# Page_1.net
KiCad netlist of a schematic drawn in Altium Designer
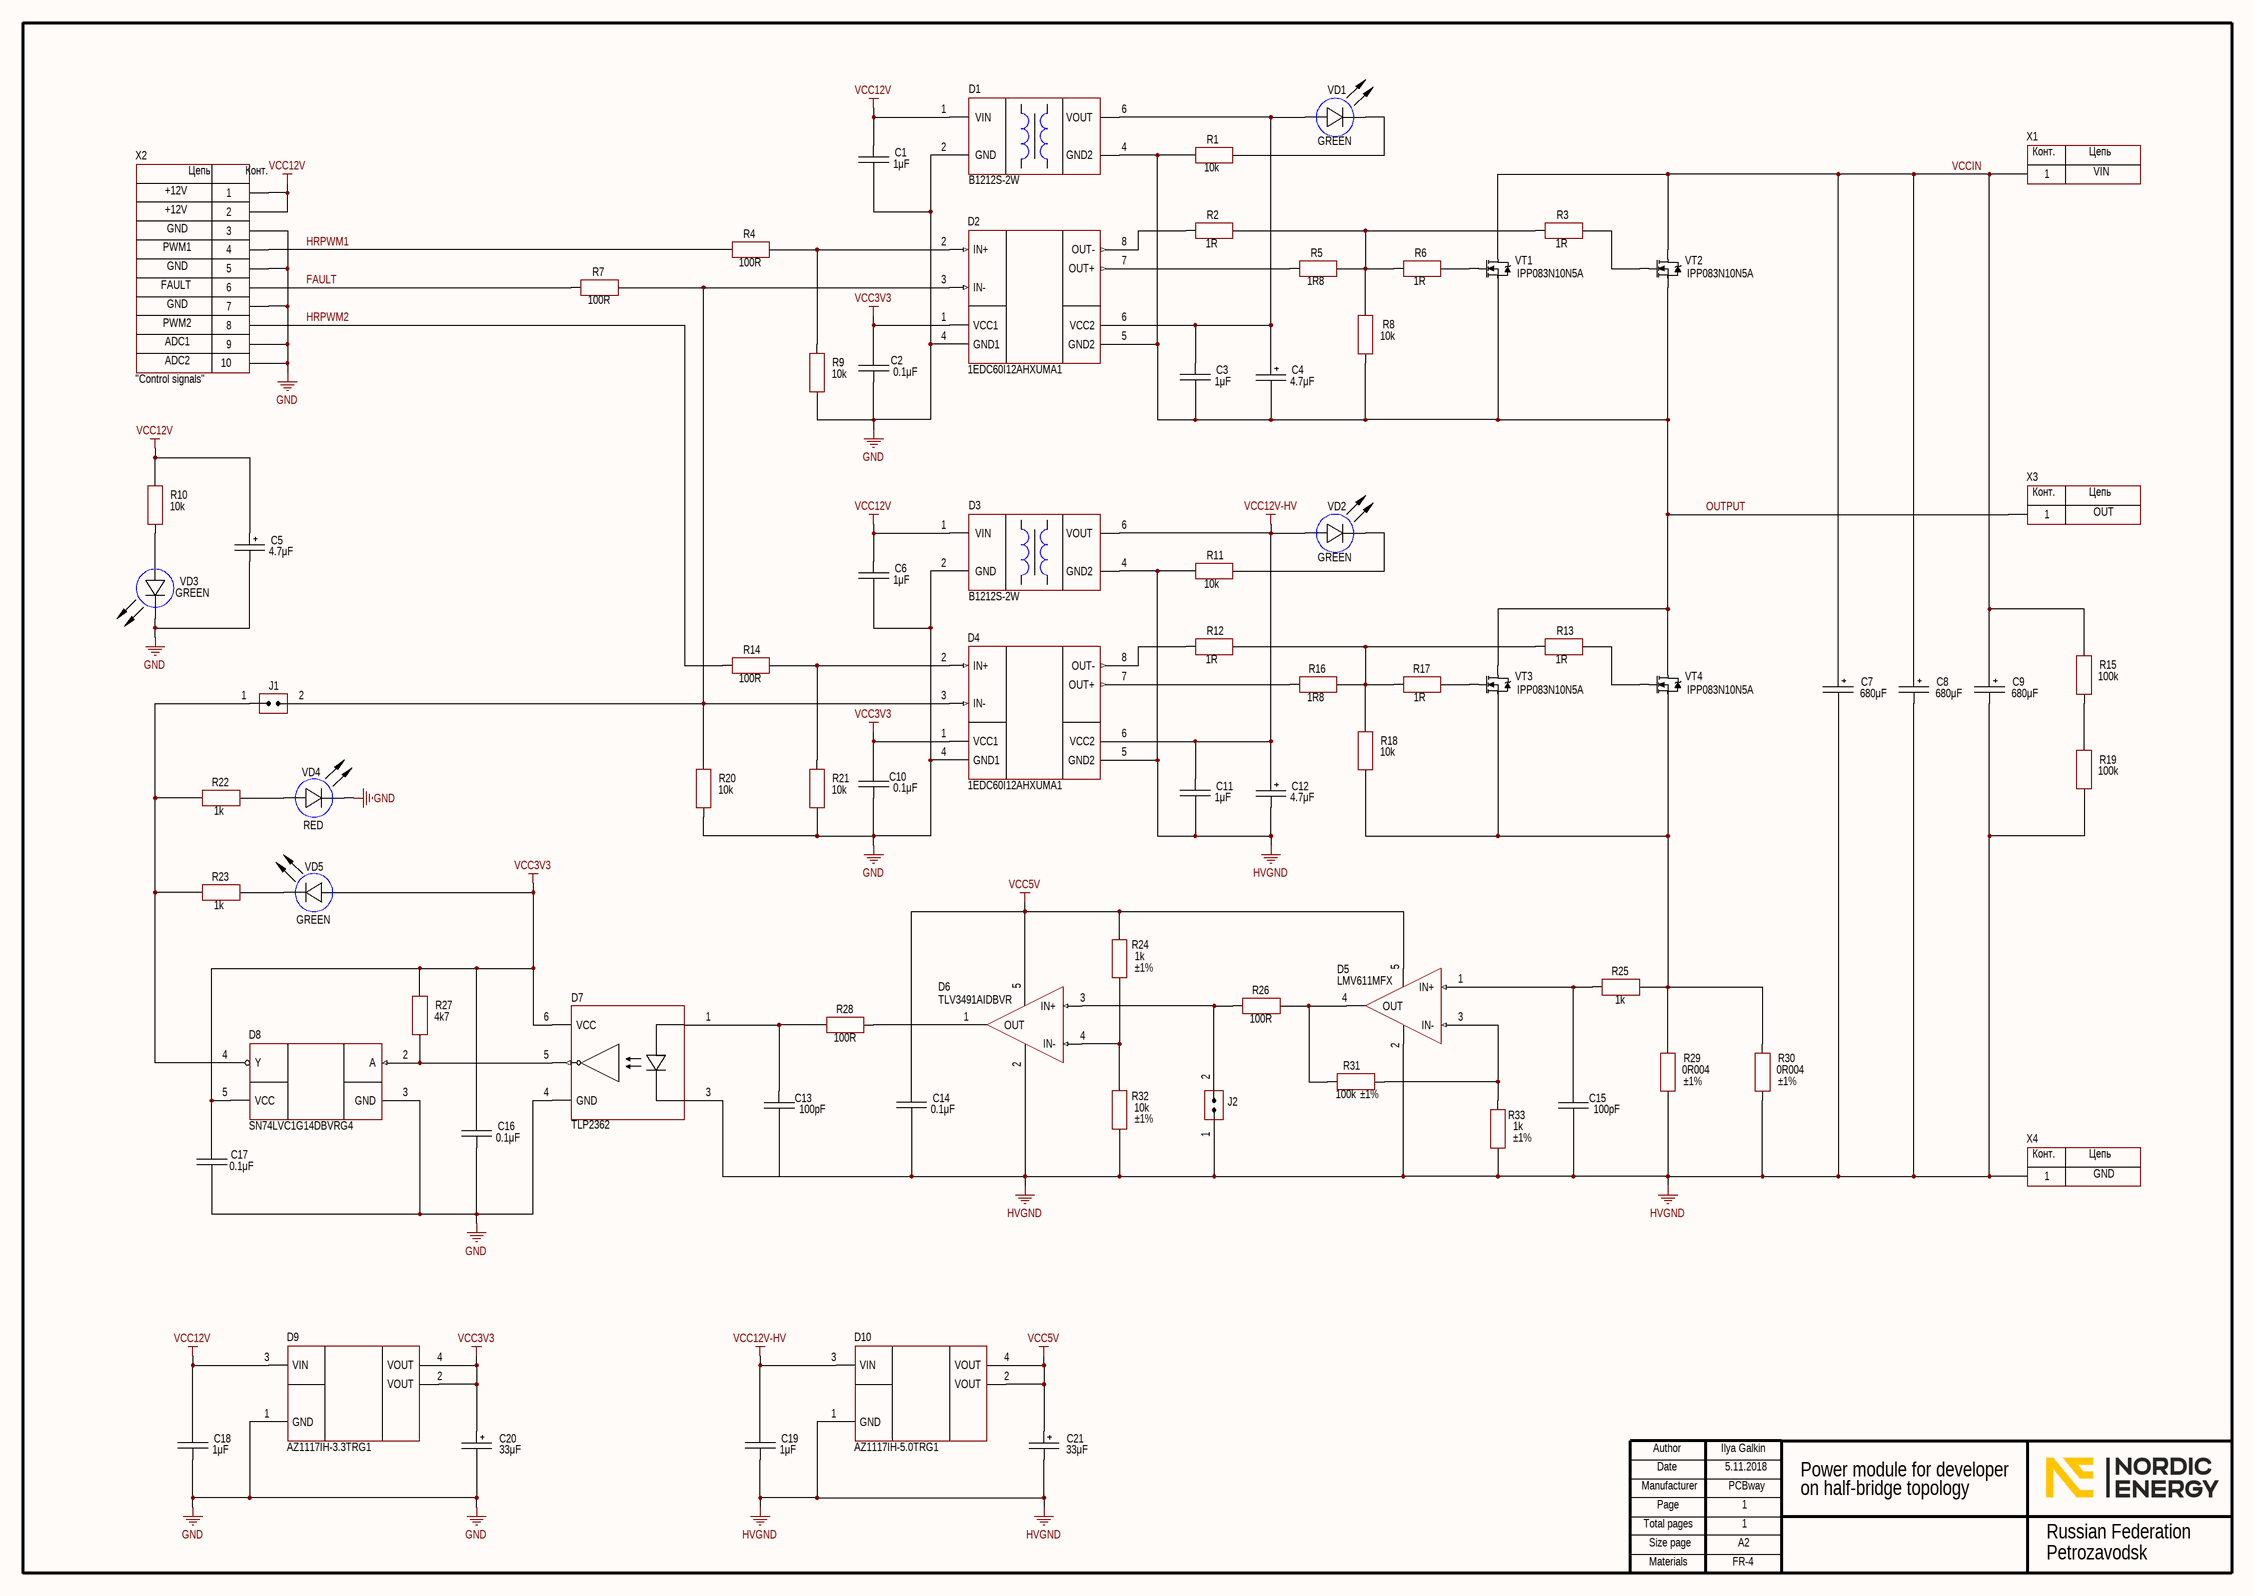
[diagram p0: Page 1.SchDoc]

(export (version "E")
  (design (tool "Eeschema 10.0.6"))
  (components
    (comp (ref "C1")
      (value "1μF")
      (footprint "CH0805C")
      (fields (field (name "MANUFACTURER") "Yageo"))
      (libsource (lib "Discrete") (part "Capacitor"))
    )
    (comp (ref "C2")
      (value "0.1μF")
      (footprint "CH0805C")
      (fields (field (name "MANUFACTURER") "Yageo"))
      (libsource (lib "Discrete") (part "Capacitor"))
    )
    (comp (ref "C3")
      (value "1μF")
      (footprint "CH0805C")
      (fields (field (name "MANUFACTURER") "Yageo"))
      (libsource (lib "Discrete") (part "Capacitor"))
    )
    (comp (ref "C4")
      (value "4.7μF")
      (footprint "TANTAL_A")
      (fields (field (name "MANUFACTURER") "KEMET"))
      (libsource (lib "Discrete") (part "TantalCap"))
    )
    (comp (ref "C5")
      (value "4.7μF")
      (footprint "TANTAL_A")
      (fields (field (name "MANUFACTURER") "KEMET"))
      (libsource (lib "Discrete") (part "TantalCap"))
    )
    (comp (ref "C6")
      (value "1μF")
      (footprint "CH0805C")
      (fields (field (name "MANUFACTURER") "Yageo"))
      (libsource (lib "Discrete") (part "Capacitor"))
    )
    (comp (ref "C7")
      (value "680μF")
      (footprint "D22C10.5H25")
      (fields (field (name "MANUFACTURER") "Yageo"))
      (libsource (lib "Discrete") (part "AlumCap"))
    )
    (comp (ref "C8")
      (value "680μF")
      (footprint "D22C10.5H25")
      (fields (field (name "MANUFACTURER") "Yageo"))
      (libsource (lib "Discrete") (part "AlumCap"))
    )
    (comp (ref "C9")
      (value "680μF")
      (footprint "D22C10.5H25")
      (fields (field (name "MANUFACTURER") "Yageo"))
      (libsource (lib "Discrete") (part "AlumCap"))
    )
    (comp (ref "C10")
      (value "0.1μF")
      (footprint "CH0805C")
      (fields (field (name "MANUFACTURER") "Yageo"))
      (libsource (lib "Discrete") (part "Capacitor"))
    )
    (comp (ref "C11")
      (value "1μF")
      (footprint "CH0805C")
      (fields (field (name "MANUFACTURER") "Yageo"))
      (libsource (lib "Discrete") (part "Capacitor"))
    )
    (comp (ref "C12")
      (value "4.7μF")
      (footprint "TANTAL_A")
      (fields (field (name "MANUFACTURER") "KEMET"))
      (libsource (lib "Discrete") (part "TantalCap"))
    )
    (comp (ref "C13")
      (value "100pF")
      (footprint "CH0805C")
      (fields (field (name "MANUFACTURER") "Yageo"))
      (libsource (lib "Discrete") (part "Capacitor"))
    )
    (comp (ref "C14")
      (value "0.1μF")
      (footprint "CH0805C")
      (fields (field (name "MANUFACTURER") "Yageo"))
      (libsource (lib "Discrete") (part "Capacitor"))
    )
    (comp (ref "C15")
      (value "100pF")
      (footprint "CH0805C")
      (fields (field (name "MANUFACTURER") "Yageo"))
      (libsource (lib "Discrete") (part "Capacitor"))
    )
    (comp (ref "C16")
      (value "0.1μF")
      (footprint "CH0805C")
      (fields (field (name "MANUFACTURER") "Yageo"))
      (libsource (lib "Discrete") (part "Capacitor"))
    )
    (comp (ref "C17")
      (value "0.1μF")
      (footprint "CH0805C")
      (fields (field (name "MANUFACTURER") "Yageo"))
      (libsource (lib "Discrete") (part "Capacitor"))
    )
    (comp (ref "C18")
      (value "1μF")
      (footprint "CH0805C")
      (fields (field (name "MANUFACTURER") "Yageo"))
      (libsource (lib "Discrete") (part "Capacitor"))
    )
    (comp (ref "C19")
      (value "1μF")
      (footprint "CH0805C")
      (fields (field (name "MANUFACTURER") "Yageo"))
      (libsource (lib "Discrete") (part "Capacitor"))
    )
    (comp (ref "C20")
      (value "33μF")
      (footprint "TANTAL_A")
      (fields (field (name "MANUFACTURER") "AVX"))
      (libsource (lib "Discrete") (part "TantalCap"))
    )
    (comp (ref "C21")
      (value "33μF")
      (footprint "TANTAL_A")
      (fields (field (name "MANUFACTURER") "AVX"))
      (libsource (lib "Discrete") (part "TantalCap"))
    )
    (comp (ref "D1")
      (value "B1212S-2W")
      (footprint "MOD: TMA-0505S")
      (description "Isolator DC")
      (fields (field (name "MANUFACTURER") "Mornsun"))
      (libsource (lib "Module") (part "TMA-0505S"))
    )
    (comp (ref "D2")
      (value "1EDC60I12AHXUMA1")
      (footprint "8-SO (300 mill)")
      (description "Driver")
      (fields (field (name "MANUFACTURER") "Infineon Technologies"))
      (libsource (lib "Power Supplies") (part "1EDC60I12AHXUMA1"))
    )
    (comp (ref "D3")
      (value "B1212S-2W")
      (footprint "MOD: TMA-0505S")
      (description "Isolator DC")
      (fields (field (name "MANUFACTURER") "Mornsun"))
      (libsource (lib "Module") (part "TMA-0505S"))
    )
    (comp (ref "D4")
      (value "1EDC60I12AHXUMA1")
      (footprint "8-SO (300 mill)")
      (description "Driver")
      (fields (field (name "MANUFACTURER") "Infineon Technologies"))
      (libsource (lib "Power Supplies") (part "1EDC60I12AHXUMA1"))
    )
    (comp (ref "D5")
      (value "LMV611MFX")
      (footprint "SOT23-5")
      (description "Amplifer")
      (fields (field (name "MANUFACTURER") "Texas Instruments"))
      (libsource (lib "Analog") (part "LMV611MFX"))
    )
    (comp (ref "D6")
      (value "TLV3491AIDBVR")
      (footprint "SOT23-5")
      (description "Comparator")
      (fields (field (name "MANUFACTURER") "Texas Instruments"))
      (libsource (lib "Analog") (part "TLV3491AIDBVR"))
    )
    (comp (ref "D7")
      (value "TLP2362")
      (footprint "OPTO: TLP2362")
      (description "Optoisolator")
      (fields (field (name "MANUFACTURER") "Toshiba"))
      (libsource (lib "Power Supplies") (part "TLP2362"))
    )
    (comp (ref "D8")
      (value "SN74LVC1G14DBVRG4")
      (footprint "SOT23-5")
      (description "Inverter logic")
      (fields (field (name "MANUFACTURER") "Texas Instruments"))
      (libsource (lib "Analog") (part "SN74LVC1G14DBVRG4"))
    )
    (comp (ref "D9")
      (value "AZ1117IH-3.3TRG1")
      (footprint "SOT223")
      (description "LDO")
      (fields (field (name "MANUFACTURER") "Diodes Incorporated"))
      (libsource (lib "Power Supplies") (part "LDL1117S33R"))
    )
    (comp (ref "D10")
      (value "AZ1117IH-5.0TRG1")
      (footprint "SOT223")
      (description "LDO")
      (fields (field (name "MANUFACTURER") "Diodes Incorporated"))
      (libsource (lib "Power Supplies") (part "LDL1117S33R"))
    )
    (comp (ref "J1")
      (value "Jumper-2")
      (footprint "CON: PLS-2")
      (description "Jumper")
      (fields (field (name "MANUFACTURER") "China"))
      (libsource (lib "Connectors") (part "Jumper-2"))
    )
    (comp (ref "J2")
      (value "Jumper-2")
      (footprint "CON: PLS-2")
      (description "Jumper")
      (fields (field (name "MANUFACTURER") "China"))
      (libsource (lib "") (part "Jumper-2_1"))
    )
    (comp (ref "R1")
      (value "10k")
      (footprint "CH0805R")
      (fields (field (name "MANUFACTURER") "Yageo"))
      (libsource (lib "") (part "Resistor_2"))
    )
    (comp (ref "R2")
      (value "1R")
      (footprint "CH0805R")
      (fields (field (name "MANUFACTURER") "Yageo"))
      (libsource (lib "Discrete") (part "Resistor"))
    )
    (comp (ref "R3")
      (value "1R")
      (footprint "CH0805R")
      (fields (field (name "MANUFACTURER") "Yageo"))
      (libsource (lib "Discrete") (part "Resistor"))
    )
    (comp (ref "R4")
      (value "100R")
      (footprint "CH0805R")
      (fields (field (name "MANUFACTURER") "Yageo"))
      (libsource (lib "Discrete") (part "Resistor"))
    )
    (comp (ref "R5")
      (value "1R8")
      (footprint "CH0805R")
      (fields (field (name "MANUFACTURER") "Yageo"))
      (libsource (lib "Discrete") (part "Resistor"))
    )
    (comp (ref "R6")
      (value "1R")
      (footprint "CH0805R")
      (fields (field (name "MANUFACTURER") "Yageo"))
      (libsource (lib "Discrete") (part "Resistor"))
    )
    (comp (ref "R7")
      (value "100R")
      (footprint "CH0805R")
      (fields (field (name "MANUFACTURER") "Yageo"))
      (libsource (lib "Discrete") (part "Resistor"))
    )
    (comp (ref "R8")
      (value "10k")
      (footprint "CH0805R")
      (fields (field (name "MANUFACTURER") "Yageo"))
      (libsource (lib "") (part "Resistor_1"))
    )
    (comp (ref "R9")
      (value "10k")
      (footprint "CH0805R")
      (fields (field (name "MANUFACTURER") "Yageo"))
      (libsource (lib "") (part "Resistor_1"))
    )
    (comp (ref "R10")
      (value "10k")
      (footprint "CH0805R")
      (fields (field (name "MANUFACTURER") "Yageo"))
      (libsource (lib "") (part "Resistor_1"))
    )
    (comp (ref "R11")
      (value "10k")
      (footprint "CH0805R")
      (fields (field (name "MANUFACTURER") "Yageo"))
      (libsource (lib "") (part "Resistor_2"))
    )
    (comp (ref "R12")
      (value "1R")
      (footprint "CH0805R")
      (fields (field (name "MANUFACTURER") "Yageo"))
      (libsource (lib "Discrete") (part "Resistor"))
    )
    (comp (ref "R13")
      (value "1R")
      (footprint "CH0805R")
      (fields (field (name "MANUFACTURER") "Yageo"))
      (libsource (lib "Discrete") (part "Resistor"))
    )
    (comp (ref "R14")
      (value "100R")
      (footprint "CH0805R")
      (fields (field (name "MANUFACTURER") "Yageo"))
      (libsource (lib "Discrete") (part "Resistor"))
    )
    (comp (ref "R15")
      (value "100k")
      (footprint "CH1206R")
      (fields (field (name "MANUFACTURER") "Yageo"))
      (libsource (lib "") (part "Resistor_1"))
    )
    (comp (ref "R16")
      (value "1R8")
      (footprint "CH0805R")
      (fields (field (name "MANUFACTURER") "Yageo"))
      (libsource (lib "Discrete") (part "Resistor"))
    )
    (comp (ref "R17")
      (value "1R")
      (footprint "CH0805R")
      (fields (field (name "MANUFACTURER") "Yageo"))
      (libsource (lib "Discrete") (part "Resistor"))
    )
    (comp (ref "R18")
      (value "10k")
      (footprint "CH0805R")
      (fields (field (name "MANUFACTURER") "Yageo"))
      (libsource (lib "") (part "Resistor_1"))
    )
    (comp (ref "R19")
      (value "100k")
      (footprint "CH1206R")
      (fields (field (name "MANUFACTURER") "Yageo"))
      (libsource (lib "") (part "Resistor_1"))
    )
    (comp (ref "R20")
      (value "10k")
      (footprint "CH0805R")
      (fields (field (name "MANUFACTURER") "Yageo"))
      (libsource (lib "") (part "Resistor_1"))
    )
    (comp (ref "R21")
      (value "10k")
      (footprint "CH0805R")
      (fields (field (name "MANUFACTURER") "Yageo"))
      (libsource (lib "") (part "Resistor_1"))
    )
    (comp (ref "R22")
      (value "1k")
      (footprint "CH0805R")
      (fields (field (name "MANUFACTURER") "Yageo"))
      (libsource (lib "") (part "Resistor_2"))
    )
    (comp (ref "R23")
      (value "1k")
      (footprint "CH0805R")
      (fields (field (name "MANUFACTURER") "Yageo"))
      (libsource (lib "") (part "Resistor_2"))
    )
    (comp (ref "R24")
      (value "1k")
      (footprint "CH0805R")
      (fields (field (name "MANUFACTURER") "Yageo") (field (name "COMPONENTKIND") "±1%"))
      (libsource (lib "Discrete") (part "Resistor"))
    )
    (comp (ref "R25")
      (value "1k")
      (footprint "CH0805R")
      (fields (field (name "MANUFACTURER") "Yageo"))
      (libsource (lib "Discrete") (part "Resistor"))
    )
    (comp (ref "R26")
      (value "100R")
      (footprint "CH0805R")
      (fields (field (name "MANUFACTURER") "Yageo"))
      (libsource (lib "Discrete") (part "Resistor"))
    )
    (comp (ref "R27")
      (value "4k7")
      (footprint "CH0805R")
      (fields (field (name "MANUFACTURER") "Yageo"))
      (libsource (lib "") (part "Resistor_1"))
    )
    (comp (ref "R28")
      (value "100R")
      (footprint "CH0805R")
      (fields (field (name "MANUFACTURER") "Yageo"))
      (libsource (lib "Discrete") (part "Resistor"))
    )
    (comp (ref "R29")
      (value "0R004")
      (footprint "CH2512R")
      (fields (field (name "MANUFACTURER") "Yageo") (field (name "COMPONENTKIND") "±1%"))
      (libsource (lib "") (part "Resistor_3"))
    )
    (comp (ref "R30")
      (value "0R004")
      (footprint "CH2512R")
      (fields (field (name "MANUFACTURER") "Yageo") (field (name "COMPONENTKIND") "±1%"))
      (libsource (lib "") (part "Resistor_3"))
    )
    (comp (ref "R31")
      (value "100k")
      (footprint "CH0805R")
      (fields (field (name "MANUFACTURER") "Yageo") (field (name "COMPONENTKIND") "±1%"))
      (libsource (lib "") (part "Resistor_3"))
    )
    (comp (ref "R32")
      (value "10k")
      (footprint "CH0805R")
      (fields (field (name "MANUFACTURER") "Yageo") (field (name "COMPONENTKIND") "±1%"))
      (libsource (lib "Discrete") (part "Resistor"))
    )
    (comp (ref "R33")
      (value "1k")
      (footprint "CH0805R")
      (fields (field (name "MANUFACTURER") "Yageo") (field (name "COMPONENTKIND") "±1%"))
      (libsource (lib "Discrete") (part "Resistor"))
    )
    (comp (ref "VD1")
      (value "GREEN")
      (footprint "CH0805LG")
      (fields (field (name "MANUFACTURER") "Wurth Electronics Inc."))
      (libsource (lib "Discrete") (part "LED"))
    )
    (comp (ref "VD2")
      (value "GREEN")
      (footprint "CH0805LG")
      (fields (field (name "MANUFACTURER") "Wurth Electronics Inc."))
      (libsource (lib "Discrete") (part "LED"))
    )
    (comp (ref "VD3")
      (value "GREEN")
      (footprint "CH0805LG")
      (fields (field (name "MANUFACTURER") "Wurth Electronics Inc."))
      (libsource (lib "Discrete") (part "LED"))
    )
    (comp (ref "VD4")
      (value "RED")
      (footprint "CH0805LR")
      (fields (field (name "MANUFACTURER") "Wurth Electronics Inc."))
      (libsource (lib "Discrete") (part "LED"))
    )
    (comp (ref "VD5")
      (value "GREEN")
      (footprint "CH0805LG")
      (fields (field (name "MANUFACTURER") "Wurth Electronics Inc."))
      (libsource (lib "Discrete") (part "LED"))
    )
    (comp (ref "VT1")
      (value "IPP083N10N5A")
      (footprint "TO220_123")
      (description "Mosfet")
      (fields (field (name "MANUFACTURER") "Infineon"))
      (libsource (lib "Transistor") (part "N-chanel"))
    )
    (comp (ref "VT2")
      (value "IPP083N10N5A")
      (footprint "TO220_123")
      (description "Mosfet")
      (fields (field (name "MANUFACTURER") "Infineon"))
      (libsource (lib "Transistor") (part "N-chanel"))
    )
    (comp (ref "VT3")
      (value "IPP083N10N5A")
      (footprint "TO220_123")
      (description "Mosfet")
      (fields (field (name "MANUFACTURER") "Infineon"))
      (libsource (lib "Transistor") (part "N-chanel"))
    )
    (comp (ref "VT4")
      (value "IPP083N10N5A")
      (footprint "TO220_123")
      (description "Mosfet")
      (fields (field (name "MANUFACTURER") "Infineon"))
      (libsource (lib "Transistor") (part "N-chanel"))
    )
    (comp (ref "X1")
      (value "~")
      (footprint "CON: 10x6 mm")
      (libsource (lib "Connectors") (part "1-Connector"))
    )
    (comp (ref "X2")
      (value "\"Control signals\"")
      (footprint "CON: BH-10")
      (fields (field (name "MANUFACTURER") "Connfly"))
      (libsource (lib "Connectors") (part "10-Connector"))
    )
    (comp (ref "X3")
      (value "~")
      (footprint "CON: 10x6 mm")
      (libsource (lib "Connectors") (part "1-Connector"))
    )
    (comp (ref "X4")
      (value "~")
      (footprint "CON: 10x6 mm")
      (libsource (lib "Connectors") (part "1-Connector"))
    )
  )
  (nets
    (net (code "1") (name "/FAULT") (class "Default")
      (node (ref "R7") (pin "1") (pinfunction "1_1") (pintype "passive"))
      (node (ref "X2") (pin "6") (pinfunction "6_6") (pintype "power_in"))
    )
    (net (code "2") (name "/HRPWM1") (class "Default")
      (node (ref "R4") (pin "1") (pinfunction "1_1") (pintype "passive"))
      (node (ref "X2") (pin "4") (pinfunction "4_4") (pintype "power_in"))
    )
    (net (code "3") (name "/HRPWM2") (class "Default")
      (node (ref "R14") (pin "1") (pinfunction "1_1") (pintype "passive"))
      (node (ref "X2") (pin "8") (pinfunction "8_8") (pintype "power_in"))
    )
    (net (code "4") (name "/OUTPUT") (class "Default")
      (node (ref "C3") (pin "1") (pinfunction "1_1") (pintype "power_in"))
      (node (ref "C4") (pin "2") (pinfunction "2_2") (pintype "power_in"))
      (node (ref "D1") (pin "4") (pinfunction "GND2_4") (pintype "power_in"))
      (node (ref "D2") (pin "5") (pinfunction "GND2_5") (pintype "passive"))
      (node (ref "R1") (pin "2") (pinfunction "2_2") (pintype "passive"))
      (node (ref "R8") (pin "1") (pinfunction "1_1") (pintype "passive"))
      (node (ref "VT1") (pin "3") (pinfunction "S_3") (pintype "passive"))
      (node (ref "VT2") (pin "3") (pinfunction "S_3") (pintype "passive"))
      (node (ref "VT3") (pin "2") (pinfunction "D_2") (pintype "passive"))
      (node (ref "VT4") (pin "2") (pinfunction "D_2") (pintype "passive"))
      (node (ref "X3") (pin "1") (pinfunction "1_1") (pintype "passive"))
    )
    (net (code "5") (name "/VCCIN") (class "Default")
      (node (ref "C7") (pin "1") (pinfunction "1_1") (pintype "power_in"))
      (node (ref "C8") (pin "1") (pinfunction "1_1") (pintype "power_in"))
      (node (ref "C9") (pin "1") (pinfunction "1_1") (pintype "power_in"))
      (node (ref "R15") (pin "2") (pinfunction "2_2") (pintype "passive"))
      (node (ref "VT1") (pin "2") (pinfunction "D_2") (pintype "passive"))
      (node (ref "VT2") (pin "2") (pinfunction "D_2") (pintype "passive"))
      (node (ref "X1") (pin "1") (pinfunction "1_1") (pintype "passive"))
    )
    (net (code "6") (name "GND") (class "Default")
      (node (ref "C1") (pin "1") (pinfunction "1_1") (pintype "power_in"))
      (node (ref "C10") (pin "1") (pinfunction "1_1") (pintype "power_in"))
      (node (ref "C16") (pin "1") (pinfunction "1_1") (pintype "power_in"))
      (node (ref "C17") (pin "1") (pinfunction "1_1") (pintype "power_in"))
      (node (ref "C18") (pin "1") (pinfunction "1_1") (pintype "power_in"))
      (node (ref "C2") (pin "1") (pinfunction "1_1") (pintype "power_in"))
      (node (ref "C20") (pin "2") (pinfunction "2_2") (pintype "power_in"))
      (node (ref "C5") (pin "2") (pinfunction "2_2") (pintype "power_in"))
      (node (ref "C6") (pin "1") (pinfunction "1_1") (pintype "power_in"))
      (node (ref "D1") (pin "2") (pinfunction "GND_2") (pintype "power_in"))
      (node (ref "D2") (pin "4") (pinfunction "GND1_4") (pintype "passive"))
      (node (ref "D3") (pin "2") (pinfunction "GND_2") (pintype "power_in"))
      (node (ref "D4") (pin "4") (pinfunction "GND1_4") (pintype "passive"))
      (node (ref "D7") (pin "4") (pinfunction "GND_4") (pintype "passive"))
      (node (ref "D8") (pin "3") (pinfunction "GND_3") (pintype "passive"))
      (node (ref "D9") (pin "1") (pinfunction "GND_1") (pintype "power_in"))
      (node (ref "R20") (pin "1") (pinfunction "1_1") (pintype "passive"))
      (node (ref "R21") (pin "1") (pinfunction "1_1") (pintype "passive"))
      (node (ref "R9") (pin "1") (pinfunction "1_1") (pintype "passive"))
      (node (ref "VD3") (pin "2") (pinfunction "C_2") (pintype "passive"))
      (node (ref "VD4") (pin "2") (pinfunction "C_2") (pintype "passive"))
      (node (ref "X2") (pin "10") (pinfunction "10_10") (pintype "power_in"))
      (node (ref "X2") (pin "3") (pinfunction "3_3") (pintype "power_in"))
      (node (ref "X2") (pin "5") (pinfunction "5_5") (pintype "power_in"))
      (node (ref "X2") (pin "7") (pinfunction "7_7") (pintype "power_in"))
      (node (ref "X2") (pin "9") (pinfunction "9_9") (pintype "power_in"))
    )
    (net (code "7") (name "HVGND") (class "Default")
      (node (ref "C11") (pin "1") (pinfunction "1_1") (pintype "power_in"))
      (node (ref "C12") (pin "2") (pinfunction "2_2") (pintype "power_in"))
      (node (ref "C13") (pin "1") (pinfunction "1_1") (pintype "power_in"))
      (node (ref "C14") (pin "1") (pinfunction "1_1") (pintype "power_in"))
      (node (ref "C15") (pin "1") (pinfunction "1_1") (pintype "power_in"))
      (node (ref "C19") (pin "1") (pinfunction "1_1") (pintype "power_in"))
      (node (ref "C21") (pin "2") (pinfunction "2_2") (pintype "power_in"))
      (node (ref "C7") (pin "2") (pinfunction "2_2") (pintype "power_in"))
      (node (ref "C8") (pin "2") (pinfunction "2_2") (pintype "power_in"))
      (node (ref "C9") (pin "2") (pinfunction "2_2") (pintype "power_in"))
      (node (ref "D10") (pin "1") (pinfunction "GND_1") (pintype "power_in"))
      (node (ref "D3") (pin "4") (pinfunction "GND2_4") (pintype "power_in"))
      (node (ref "D4") (pin "5") (pinfunction "GND2_5") (pintype "passive"))
      (node (ref "D5") (pin "2") (pinfunction "V-_2") (pintype "power_in"))
      (node (ref "D6") (pin "2") (pinfunction "V-_2") (pintype "power_in"))
      (node (ref "D7") (pin "3") (pinfunction "C_3") (pintype "passive"))
      (node (ref "J2") (pin "1") (pinfunction "IN_1") (pintype "passive"))
      (node (ref "R11") (pin "2") (pinfunction "2_2") (pintype "passive"))
      (node (ref "R19") (pin "1") (pinfunction "1_1") (pintype "passive"))
      (node (ref "R29") (pin "2") (pinfunction "2_2") (pintype "passive"))
      (node (ref "R30") (pin "2") (pinfunction "2_2") (pintype "passive"))
      (node (ref "R32") (pin "1") (pinfunction "1_1") (pintype "passive"))
      (node (ref "R33") (pin "1") (pinfunction "1_1") (pintype "passive"))
      (node (ref "X4") (pin "1") (pinfunction "1_1") (pintype "passive"))
    )
    (net (code "8") (name "Net-(D1-VOUT)") (class "Default")
      (node (ref "C3") (pin "2") (pinfunction "2_2") (pintype "power_in"))
      (node (ref "C4") (pin "1") (pinfunction "1_1") (pintype "power_in"))
      (node (ref "D1") (pin "6") (pinfunction "VOUT_6") (pintype "power_in"))
      (node (ref "D2") (pin "6") (pinfunction "VCC2_6") (pintype "passive"))
      (node (ref "VD1") (pin "1") (pinfunction "A_1") (pintype "passive"))
    )
    (net (code "9") (name "Net-(D2-IN+)") (class "Default")
      (node (ref "D2") (pin "2") (pinfunction "IN+_2") (pintype "input"))
      (node (ref "R4") (pin "2") (pinfunction "2_2") (pintype "passive"))
      (node (ref "R9") (pin "2") (pinfunction "2_2") (pintype "passive"))
    )
    (net (code "10") (name "Net-(D2-IN-)") (class "Default")
      (node (ref "D2") (pin "3") (pinfunction "IN-_3") (pintype "input"))
      (node (ref "D4") (pin "3") (pinfunction "IN-_3") (pintype "input"))
      (node (ref "J1") (pin "2") (pinfunction "IN_2") (pintype "passive"))
      (node (ref "R20") (pin "2") (pinfunction "2_2") (pintype "passive"))
      (node (ref "R7") (pin "2") (pinfunction "2_2") (pintype "passive"))
    )
    (net (code "11") (name "Net-(D2-OUT+)") (class "Default")
      (node (ref "D2") (pin "7") (pinfunction "OUT+_7") (pintype "output"))
      (node (ref "R5") (pin "1") (pinfunction "1_1") (pintype "passive"))
    )
    (net (code "12") (name "Net-(D2-OUT-)") (class "Default")
      (node (ref "D2") (pin "8") (pinfunction "OUT-_8") (pintype "output"))
      (node (ref "R2") (pin "1") (pinfunction "1_1") (pintype "passive"))
    )
    (net (code "13") (name "Net-(D4-IN+)") (class "Default")
      (node (ref "D4") (pin "2") (pinfunction "IN+_2") (pintype "input"))
      (node (ref "R14") (pin "2") (pinfunction "2_2") (pintype "passive"))
      (node (ref "R21") (pin "2") (pinfunction "2_2") (pintype "passive"))
    )
    (net (code "14") (name "Net-(D4-OUT+)") (class "Default")
      (node (ref "D4") (pin "7") (pinfunction "OUT+_7") (pintype "output"))
      (node (ref "R16") (pin "1") (pinfunction "1_1") (pintype "passive"))
    )
    (net (code "15") (name "Net-(D4-OUT-)") (class "Default")
      (node (ref "D4") (pin "8") (pinfunction "OUT-_8") (pintype "output"))
      (node (ref "R12") (pin "1") (pinfunction "1_1") (pintype "passive"))
    )
    (net (code "16") (name "Net-(D5-IN+)") (class "Default")
      (node (ref "C15") (pin "2") (pinfunction "2_2") (pintype "power_in"))
      (node (ref "D5") (pin "1") (pinfunction "IN+_1") (pintype "input"))
      (node (ref "R25") (pin "1") (pinfunction "1_1") (pintype "passive"))
    )
    (net (code "17") (name "Net-(D5-IN-)") (class "Default")
      (node (ref "D5") (pin "3") (pinfunction "IN-_3") (pintype "input"))
      (node (ref "R31") (pin "1") (pinfunction "1_1") (pintype "passive"))
      (node (ref "R33") (pin "2") (pinfunction "2_2") (pintype "passive"))
    )
    (net (code "18") (name "Net-(D5-OUT)") (class "Default")
      (node (ref "D5") (pin "4") (pinfunction "OUT_4") (pintype "power_in"))
      (node (ref "R26") (pin "2") (pinfunction "2_2") (pintype "passive"))
      (node (ref "R31") (pin "2") (pinfunction "2_2") (pintype "passive"))
    )
    (net (code "19") (name "Net-(D6-IN+)") (class "Default")
      (node (ref "D6") (pin "3") (pinfunction "IN+_3") (pintype "input"))
      (node (ref "J2") (pin "2") (pinfunction "IN_2") (pintype "passive"))
      (node (ref "R26") (pin "1") (pinfunction "1_1") (pintype "passive"))
    )
    (net (code "20") (name "Net-(D6-IN-)") (class "Default")
      (node (ref "D6") (pin "4") (pinfunction "IN-_4") (pintype "input"))
      (node (ref "R24") (pin "1") (pinfunction "1_1") (pintype "passive"))
      (node (ref "R32") (pin "2") (pinfunction "2_2") (pintype "passive"))
    )
    (net (code "21") (name "Net-(D6-OUT)") (class "Default")
      (node (ref "D6") (pin "1") (pinfunction "OUT_1") (pintype "power_in"))
      (node (ref "R28") (pin "2") (pinfunction "2_2") (pintype "passive"))
    )
    (net (code "22") (name "Net-(D7-A)") (class "Default")
      (node (ref "C13") (pin "2") (pinfunction "2_2") (pintype "power_in"))
      (node (ref "D7") (pin "1") (pinfunction "A_1") (pintype "passive"))
      (node (ref "R28") (pin "1") (pinfunction "1_1") (pintype "passive"))
    )
    (net (code "23") (name "Net-(D7-VOUT)") (class "Default")
      (node (ref "D7") (pin "5") (pinfunction "VOUT_5") (pintype "output"))
      (node (ref "D8") (pin "2") (pinfunction "A_2") (pintype "input"))
      (node (ref "R27") (pin "1") (pinfunction "1_1") (pintype "passive"))
    )
    (net (code "24") (name "Net-(D8-Y)") (class "Default")
      (node (ref "D8") (pin "4") (pinfunction "Y_4") (pintype "passive"))
      (node (ref "J1") (pin "1") (pinfunction "IN_1") (pintype "passive"))
      (node (ref "R22") (pin "2") (pinfunction "2_2") (pintype "passive"))
      (node (ref "R23") (pin "2") (pinfunction "2_2") (pintype "passive"))
    )
    (net (code "25") (name "Net-(R2-Pad2)") (class "Default")
      (node (ref "R2") (pin "2") (pinfunction "2_2") (pintype "passive"))
      (node (ref "R3") (pin "1") (pinfunction "1_1") (pintype "passive"))
      (node (ref "R5") (pin "2") (pinfunction "2_2") (pintype "passive"))
      (node (ref "R6") (pin "1") (pinfunction "1_1") (pintype "passive"))
      (node (ref "R8") (pin "2") (pinfunction "2_2") (pintype "passive"))
    )
    (net (code "26") (name "Net-(R12-Pad2)") (class "Default")
      (node (ref "R12") (pin "2") (pinfunction "2_2") (pintype "passive"))
      (node (ref "R13") (pin "1") (pinfunction "1_1") (pintype "passive"))
      (node (ref "R16") (pin "2") (pinfunction "2_2") (pintype "passive"))
      (node (ref "R17") (pin "1") (pinfunction "1_1") (pintype "passive"))
      (node (ref "R18") (pin "2") (pinfunction "2_2") (pintype "passive"))
    )
    (net (code "27") (name "Net-(R15-Pad1)") (class "Default")
      (node (ref "R15") (pin "1") (pinfunction "1_1") (pintype "passive"))
      (node (ref "R19") (pin "2") (pinfunction "2_2") (pintype "passive"))
    )
    (net (code "28") (name "Net-(VD1-C)") (class "Default")
      (node (ref "R1") (pin "1") (pinfunction "1_1") (pintype "passive"))
      (node (ref "VD1") (pin "2") (pinfunction "C_2") (pintype "passive"))
    )
    (net (code "29") (name "Net-(VD2-C)") (class "Default")
      (node (ref "R11") (pin "1") (pinfunction "1_1") (pintype "passive"))
      (node (ref "VD2") (pin "2") (pinfunction "C_2") (pintype "passive"))
    )
    (net (code "30") (name "Net-(VD3-A)") (class "Default")
      (node (ref "R10") (pin "1") (pinfunction "1_1") (pintype "passive"))
      (node (ref "VD3") (pin "1") (pinfunction "A_1") (pintype "passive"))
    )
    (net (code "31") (name "Net-(VD4-A)") (class "Default")
      (node (ref "R22") (pin "1") (pinfunction "1_1") (pintype "passive"))
      (node (ref "VD4") (pin "1") (pinfunction "A_1") (pintype "passive"))
    )
    (net (code "32") (name "Net-(VD5-C)") (class "Default")
      (node (ref "R23") (pin "1") (pinfunction "1_1") (pintype "passive"))
      (node (ref "VD5") (pin "2") (pinfunction "C_2") (pintype "passive"))
    )
    (net (code "33") (name "Net-(VT1-G)") (class "Default")
      (node (ref "R6") (pin "2") (pinfunction "2_2") (pintype "passive"))
      (node (ref "VT1") (pin "1") (pinfunction "G_1") (pintype "passive"))
    )
    (net (code "34") (name "Net-(VT2-G)") (class "Default")
      (node (ref "R3") (pin "2") (pinfunction "2_2") (pintype "passive"))
      (node (ref "VT2") (pin "1") (pinfunction "G_1") (pintype "passive"))
    )
    (net (code "35") (name "Net-(VT3-G)") (class "Default")
      (node (ref "R17") (pin "2") (pinfunction "2_2") (pintype "passive"))
      (node (ref "VT3") (pin "1") (pinfunction "G_1") (pintype "passive"))
    )
    (net (code "36") (name "Net-(VT3-S)") (class "Default")
      (node (ref "R18") (pin "1") (pinfunction "1_1") (pintype "passive"))
      (node (ref "R25") (pin "2") (pinfunction "2_2") (pintype "passive"))
      (node (ref "R29") (pin "1") (pinfunction "1_1") (pintype "passive"))
      (node (ref "R30") (pin "1") (pinfunction "1_1") (pintype "passive"))
      (node (ref "VT3") (pin "3") (pinfunction "S_3") (pintype "passive"))
      (node (ref "VT4") (pin "3") (pinfunction "S_3") (pintype "passive"))
    )
    (net (code "37") (name "Net-(VT4-G)") (class "Default")
      (node (ref "R13") (pin "2") (pinfunction "2_2") (pintype "passive"))
      (node (ref "VT4") (pin "1") (pinfunction "G_1") (pintype "passive"))
    )
    (net (code "38") (name "VCC3V3") (class "Default")
      (node (ref "C10") (pin "2") (pinfunction "2_2") (pintype "power_in"))
      (node (ref "C16") (pin "2") (pinfunction "2_2") (pintype "power_in"))
      (node (ref "C17") (pin "2") (pinfunction "2_2") (pintype "power_in"))
      (node (ref "C2") (pin "2") (pinfunction "2_2") (pintype "power_in"))
      (node (ref "C20") (pin "1") (pinfunction "1_1") (pintype "power_in"))
      (node (ref "D2") (pin "1") (pinfunction "VCC1_1") (pintype "passive"))
      (node (ref "D4") (pin "1") (pinfunction "VCC1_1") (pintype "passive"))
      (node (ref "D7") (pin "6") (pinfunction "VCC_6") (pintype "passive"))
      (node (ref "D8") (pin "5") (pinfunction "VCC_5") (pintype "passive"))
      (node (ref "D9") (pin "2") (pinfunction "VOUT_2") (pintype "power_in"))
      (node (ref "D9") (pin "4") (pinfunction "VOUT_4") (pintype "power_in"))
      (node (ref "R27") (pin "2") (pinfunction "2_2") (pintype "passive"))
      (node (ref "VD5") (pin "1") (pinfunction "A_1") (pintype "passive"))
    )
    (net (code "39") (name "VCC5V") (class "Default")
      (node (ref "C14") (pin "2") (pinfunction "2_2") (pintype "power_in"))
      (node (ref "C21") (pin "1") (pinfunction "1_1") (pintype "power_in"))
      (node (ref "D10") (pin "2") (pinfunction "VOUT_2") (pintype "power_in"))
      (node (ref "D10") (pin "4") (pinfunction "VOUT_4") (pintype "power_in"))
      (node (ref "D5") (pin "5") (pinfunction "V+_5") (pintype "power_in"))
      (node (ref "D6") (pin "5") (pinfunction "V+_5") (pintype "power_in"))
      (node (ref "R24") (pin "2") (pinfunction "2_2") (pintype "passive"))
    )
    (net (code "40") (name "VCC12V") (class "Default")
      (node (ref "C1") (pin "2") (pinfunction "2_2") (pintype "power_in"))
      (node (ref "C18") (pin "2") (pinfunction "2_2") (pintype "power_in"))
      (node (ref "C5") (pin "1") (pinfunction "1_1") (pintype "power_in"))
      (node (ref "C6") (pin "2") (pinfunction "2_2") (pintype "power_in"))
      (node (ref "D1") (pin "1") (pinfunction "VIN_1") (pintype "power_in"))
      (node (ref "D3") (pin "1") (pinfunction "VIN_1") (pintype "power_in"))
      (node (ref "D9") (pin "3") (pinfunction "VIN_3") (pintype "power_in"))
      (node (ref "R10") (pin "2") (pinfunction "2_2") (pintype "passive"))
      (node (ref "X2") (pin "1") (pinfunction "1_1") (pintype "passive"))
      (node (ref "X2") (pin "2") (pinfunction "2_2") (pintype "passive"))
    )
    (net (code "41") (name "VCC12V-HV") (class "Default")
      (node (ref "C11") (pin "2") (pinfunction "2_2") (pintype "power_in"))
      (node (ref "C12") (pin "1") (pinfunction "1_1") (pintype "power_in"))
      (node (ref "C19") (pin "2") (pinfunction "2_2") (pintype "power_in"))
      (node (ref "D10") (pin "3") (pinfunction "VIN_3") (pintype "power_in"))
      (node (ref "D3") (pin "6") (pinfunction "VOUT_6") (pintype "power_in"))
      (node (ref "D4") (pin "6") (pinfunction "VCC2_6") (pintype "passive"))
      (node (ref "VD2") (pin "1") (pinfunction "A_1") (pintype "passive"))
    )
  )
)
